# SparkFun_Qwiic_Soil_Moisture_Sensor.net
KiCad netlist of a schematic drawn in EAGLE
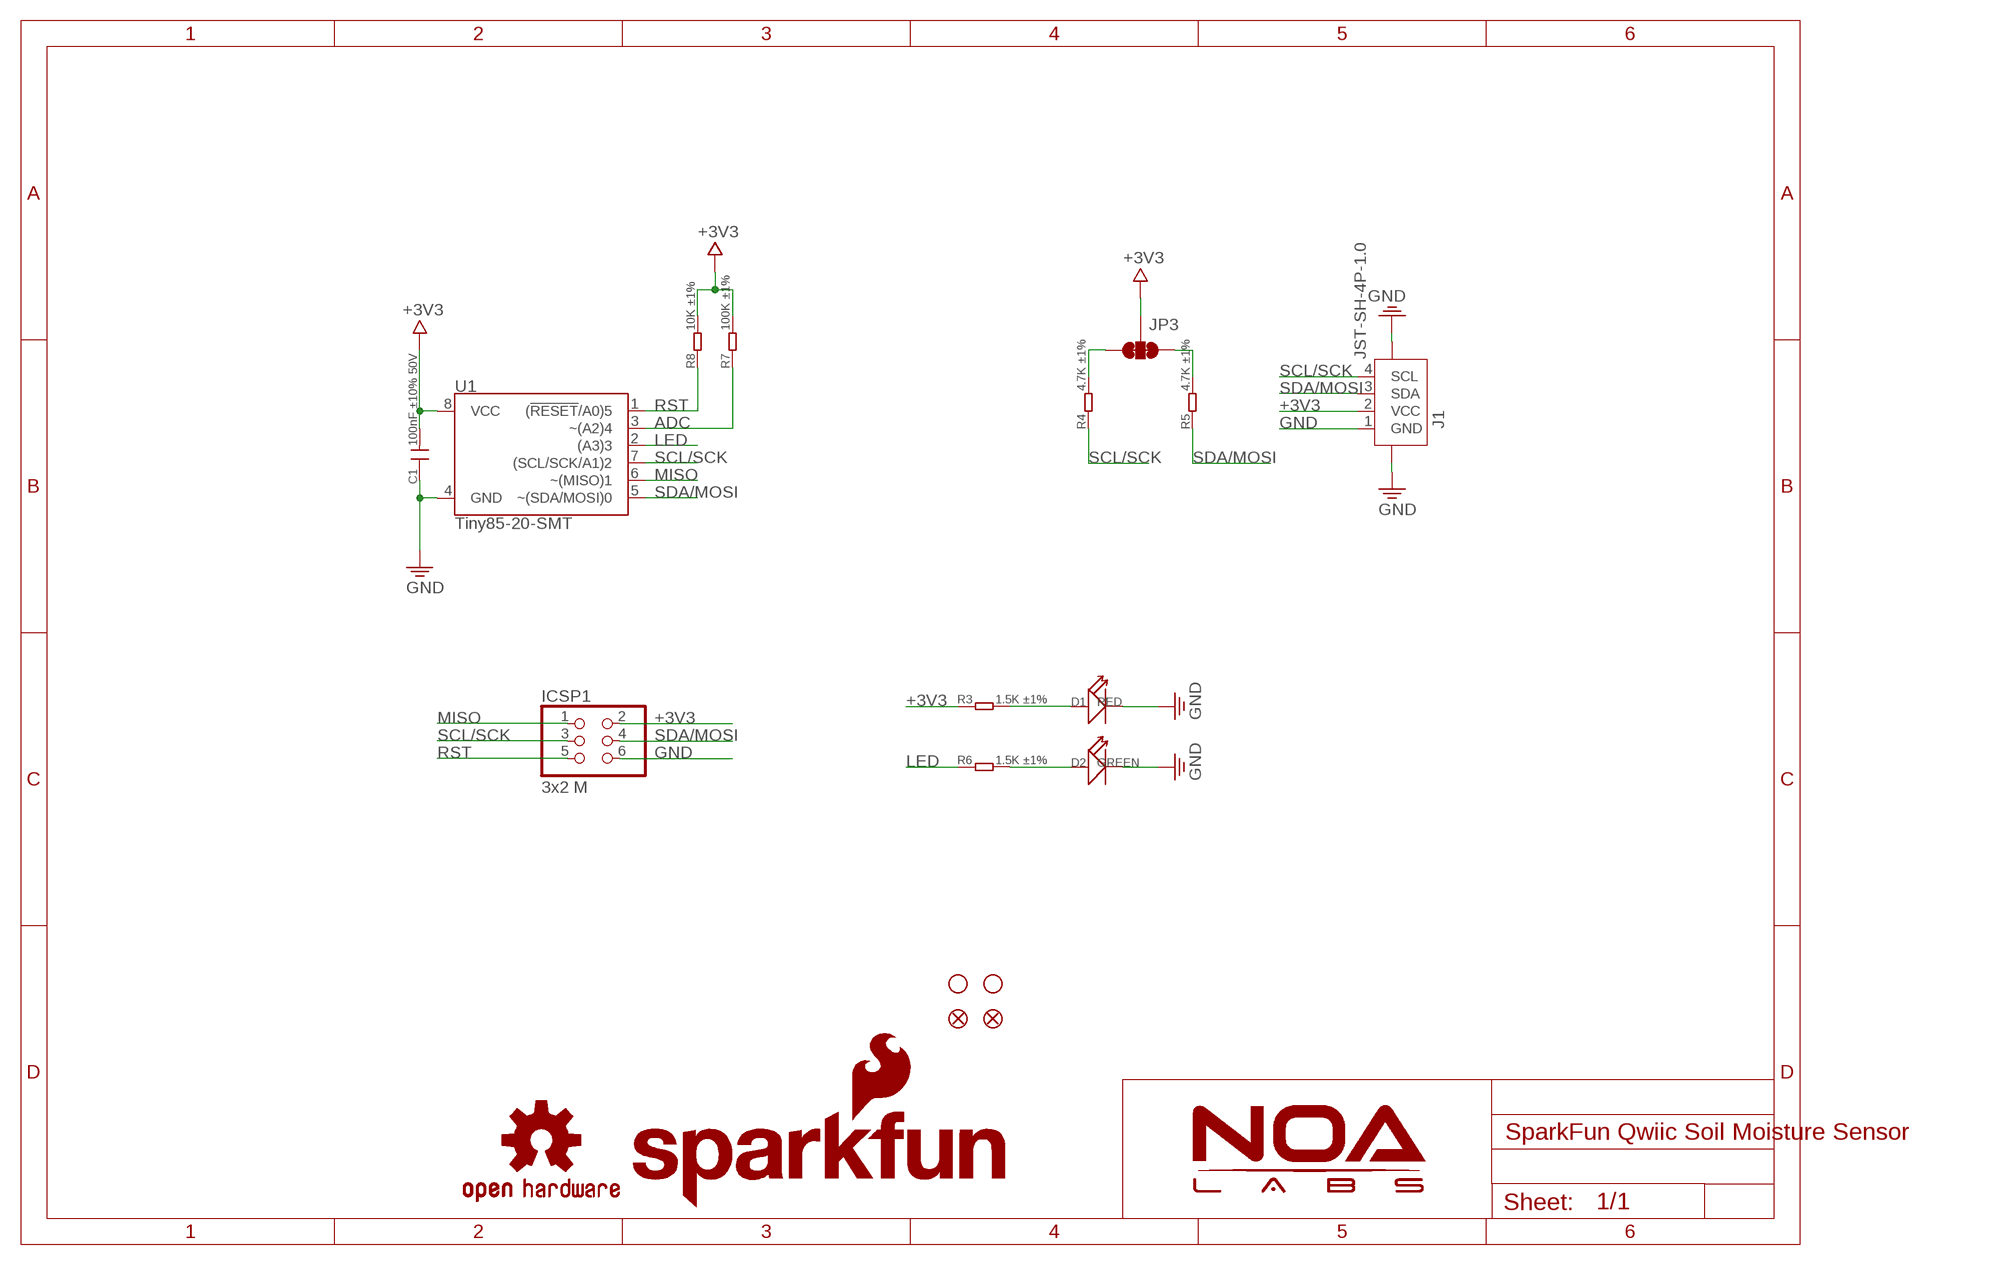
[diagram p0: schematic, sheet 1]

(export (version "E")
  (design (tool "Eeschema 10.0.6"))
  (components
    (comp (ref "C1")
      (value "100nF ±10% 50V")
      (footprint "eagle-import:C0603")
      (libsource (lib "eagle-import") (part "C-0603"))
    )
    (comp (ref "D1")
      (value "RED")
      (footprint "eagle-import:LED-0603")
      (libsource (lib "eagle-import") (part "LED'0603'"))
    )
    (comp (ref "D2")
      (value "GREEN")
      (footprint "eagle-import:LED-0603")
      (libsource (lib "eagle-import") (part "LED'0603'"))
    )
    (comp (ref "FID1")
      (value "FIDUCIAL1X2")
      (footprint "eagle-import:FIDUCIAL-1X2")
      (libsource (lib "eagle-import") (part "FIDUCIAL1X2"))
    )
    (comp (ref "FID2")
      (value "FIDUCIAL1X2")
      (footprint "eagle-import:FIDUCIAL-1X2")
      (libsource (lib "eagle-import") (part "FIDUCIAL1X2"))
    )
    (comp (ref "ICSP1")
      (value "3x2 M")
      (footprint "eagle-import:2X03")
      (libsource (lib "eagle-import") (part "PINHD-2X3"))
    )
    (comp (ref "J1")
      (value "JST-SH-4P-1.0")
      (footprint "eagle-import:JST-SH-4P")
      (libsource (lib "eagle-import") (part "JST-SH-4P-1.0"))
    )
    (comp (ref "JP3")
      (value "SMT-JUMPER_3_2-NC_TRACE")
      (footprint "eagle-import:SMT-JUMPER_3_2-NC_TRACE")
      (libsource (lib "eagle-import") (part "SMT-JUMPER_3_2-NC_TRACE"))
    )
    (comp (ref "LOGO1")
      (value "SFE_LOGO_NAME_FLAME.1_INCH")
      (footprint "eagle-import:SFE_LOGO_NAME_FLAME_.1")
      (libsource (lib "eagle-import") (part "SFE_LOGO_NAME_FLAME.1_INCH"))
    )
    (comp (ref "LOGO2")
      (value "OSHW-LOGOS")
      (footprint "eagle-import:OSHW-LOGO-S")
      (libsource (lib "eagle-import") (part "OSHW-LOGOS"))
    )
    (comp (ref "R3")
      (value "1.5K ±1%")
      (footprint "eagle-import:R0603")
      (libsource (lib "eagle-import") (part "R-0603"))
    )
    (comp (ref "R4")
      (value "4.7K ±1%")
      (footprint "eagle-import:R0603")
      (libsource (lib "eagle-import") (part "R-0603"))
    )
    (comp (ref "R5")
      (value "4.7K ±1%")
      (footprint "eagle-import:R0603")
      (libsource (lib "eagle-import") (part "R-0603"))
    )
    (comp (ref "R6")
      (value "1.5K ±1%")
      (footprint "eagle-import:R0603")
      (libsource (lib "eagle-import") (part "R-0603"))
    )
    (comp (ref "R7")
      (value "100K ±1%")
      (footprint "eagle-import:R0603")
      (libsource (lib "eagle-import") (part "R-0603"))
    )
    (comp (ref "R8")
      (value "10K ±1%")
      (footprint "eagle-import:R0603")
      (libsource (lib "eagle-import") (part "R-0603"))
    )
    (comp (ref "STANDOFF1")
      (value "STAND-OFF")
      (footprint "eagle-import:STAND-OFF")
      (libsource (lib "eagle-import") (part "STAND-OFF"))
    )
    (comp (ref "STANDOFF2")
      (value "STAND-OFF")
      (footprint "eagle-import:STAND-OFF")
      (libsource (lib "eagle-import") (part "STAND-OFF"))
    )
    (comp (ref "U1")
      (value "Tiny85-20-SMT")
      (footprint "eagle-import:SO08-EIAJ_MCU")
      (libsource (lib "eagle-import") (part "ATTINY85-ARDUINOTINY85-20-SMT"))
    )
  )
  (nets
    (net (code "1") (name "+3V3") (class "Default")
      (node (ref "C1") (pin "2") (pinfunction "2_2") (pintype "passive"))
      (node (ref "ICSP1") (pin "2") (pinfunction "2_2") (pintype "passive"))
      (node (ref "J1") (pin "2") (pinfunction "VCC_2") (pintype "bidirectional"))
      (node (ref "JP3") (pin "2") (pinfunction "2_2") (pintype "passive"))
      (node (ref "R3") (pin "1") (pinfunction "1_1") (pintype "passive"))
      (node (ref "R7") (pin "2") (pinfunction "2_2") (pintype "passive"))
      (node (ref "R8") (pin "2") (pinfunction "2_2") (pintype "passive"))
      (node (ref "U1") (pin "8") (pinfunction "VCC_8") (pintype "bidirectional"))
    )
    (net (code "2") (name "/ADC") (class "Default")
      (node (ref "R7") (pin "1") (pinfunction "1_1") (pintype "passive"))
      (node (ref "U1") (pin "3") (pinfunction "~{(A2})4_3") (pintype "bidirectional"))
    )
    (net (code "3") (name "/LED") (class "Default")
      (node (ref "R6") (pin "1") (pinfunction "1_1") (pintype "passive"))
      (node (ref "U1") (pin "2") (pinfunction "(A3)3_2") (pintype "bidirectional"))
    )
    (net (code "4") (name "/MISO") (class "Default")
      (node (ref "ICSP1") (pin "1") (pinfunction "1_1") (pintype "passive"))
      (node (ref "U1") (pin "6") (pinfunction "~{(MISO})1_6") (pintype "bidirectional"))
    )
    (net (code "5") (name "/RST") (class "Default")
      (node (ref "ICSP1") (pin "5") (pinfunction "5_5") (pintype "passive"))
      (node (ref "R8") (pin "1") (pinfunction "1_1") (pintype "passive"))
      (node (ref "U1") (pin "1") (pinfunction "(~{RESET}/A0)5_1") (pintype "bidirectional"))
    )
    (net (code "6") (name "/SCL{slash}SCK") (class "Default")
      (node (ref "ICSP1") (pin "3") (pinfunction "3_3") (pintype "passive"))
      (node (ref "J1") (pin "4") (pinfunction "SCL_4") (pintype "bidirectional"))
      (node (ref "R4") (pin "1") (pinfunction "1_1") (pintype "passive"))
      (node (ref "U1") (pin "7") (pinfunction "(SCL/SCK/A1)2_7") (pintype "bidirectional"))
    )
    (net (code "7") (name "/SDA{slash}MOSI") (class "Default")
      (node (ref "ICSP1") (pin "4") (pinfunction "4_4") (pintype "passive"))
      (node (ref "J1") (pin "3") (pinfunction "SDA_3") (pintype "bidirectional"))
      (node (ref "R5") (pin "1") (pinfunction "1_1") (pintype "passive"))
      (node (ref "U1") (pin "5") (pinfunction "~{(SDA/MOSI})0_5") (pintype "bidirectional"))
    )
    (net (code "8") (name "GND") (class "Default")
      (node (ref "C1") (pin "1") (pinfunction "1_1") (pintype "passive"))
      (node (ref "D1") (pin "-") (pinfunction "-_-") (pintype "passive"))
      (node (ref "D2") (pin "-") (pinfunction "-_-") (pintype "passive"))
      (node (ref "ICSP1") (pin "6") (pinfunction "6_6") (pintype "passive"))
      (node (ref "J1") (pin "1") (pinfunction "GND_1") (pintype "bidirectional"))
      (node (ref "J1") (pin "NC1") (pinfunction "5_NC1") (pintype "bidirectional"))
      (node (ref "J1") (pin "NC2") (pinfunction "6_NC2") (pintype "bidirectional"))
      (node (ref "U1") (pin "4") (pinfunction "GND_4") (pintype "bidirectional"))
    )
    (net (code "9") (name "Net-(D1-Pad+)") (class "Default")
      (node (ref "D1") (pin "+") (pinfunction "+_+") (pintype "passive"))
      (node (ref "R3") (pin "2") (pinfunction "2_2") (pintype "passive"))
    )
    (net (code "10") (name "Net-(D2-Pad+)") (class "Default")
      (node (ref "D2") (pin "+") (pinfunction "+_+") (pintype "passive"))
      (node (ref "R6") (pin "2") (pinfunction "2_2") (pintype "passive"))
    )
    (net (code "11") (name "Net-(JP3-Pad1)") (class "Default")
      (node (ref "JP3") (pin "1") (pinfunction "1_1") (pintype "passive"))
      (node (ref "R5") (pin "2") (pinfunction "2_2") (pintype "passive"))
    )
    (net (code "12") (name "Net-(JP3-Pad3)") (class "Default")
      (node (ref "JP3") (pin "3") (pinfunction "3_3") (pintype "passive"))
      (node (ref "R4") (pin "2") (pinfunction "2_2") (pintype "passive"))
    )
  )
)
